# Sheet1.net
KiCad netlist of a schematic drawn in Altium Designer
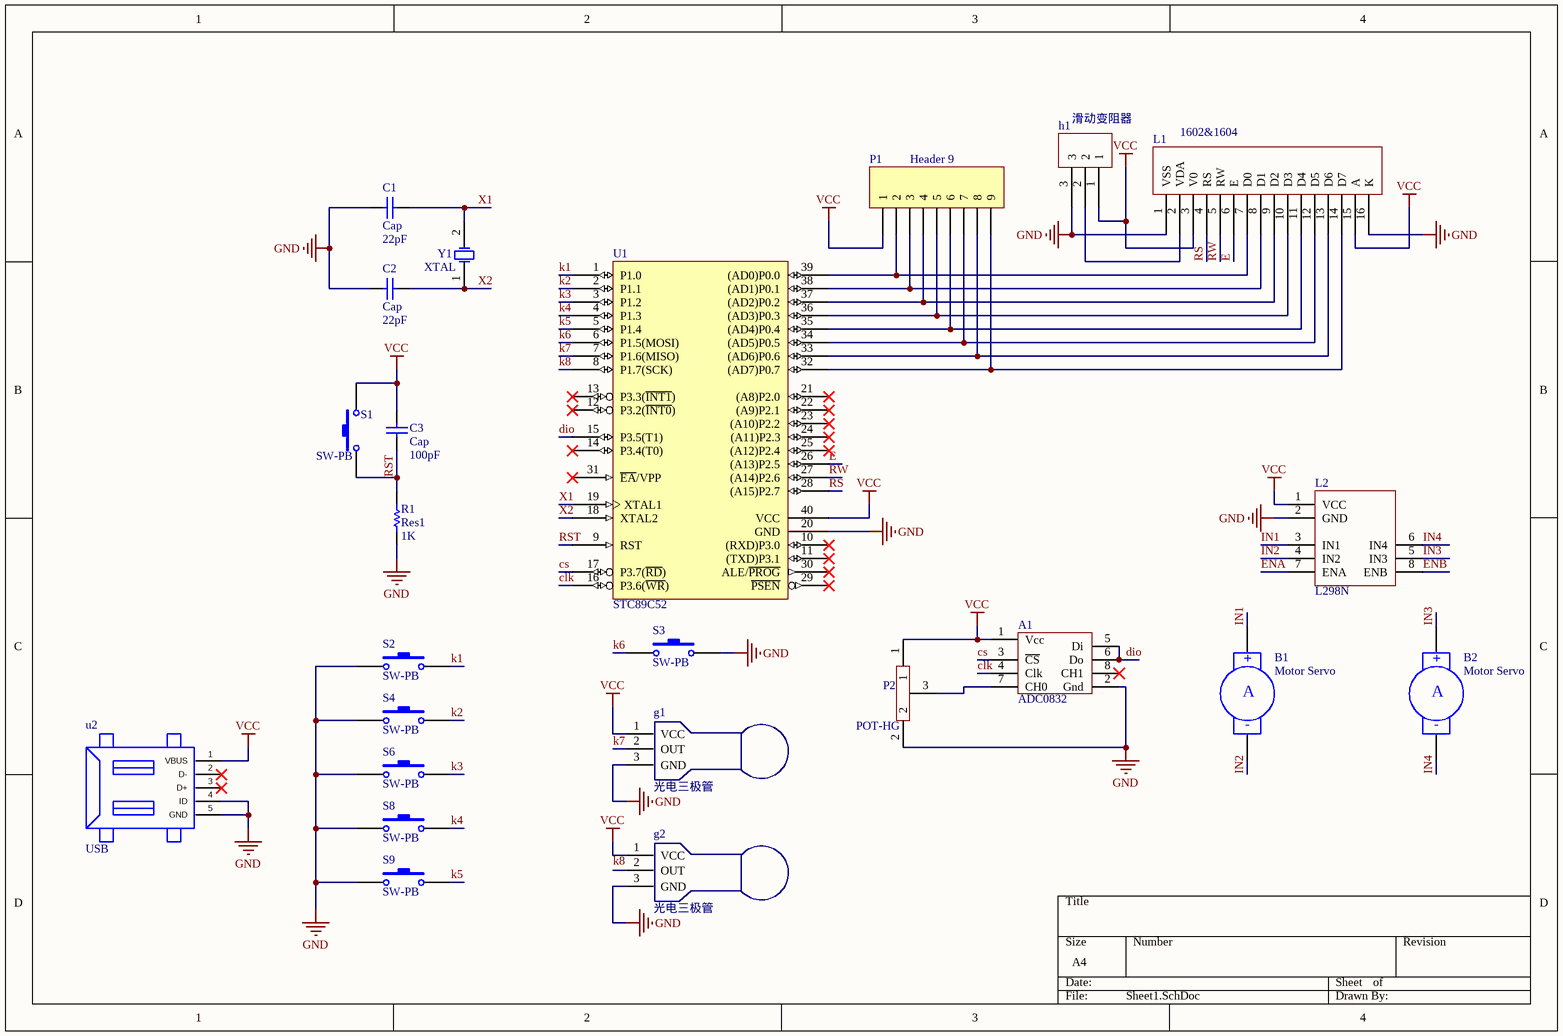
[diagram p0: Sheet1.SchDoc]

(export (version "E")
  (design (tool "Eeschema 10.0.6"))
  (components
    (comp (ref "A1") (value "ADC0832") (libsource (lib "mine") (part "ADC0832")))
    (comp (ref "B1")
      (value "Motor Servo")
      (footprint "RAD-0.4")
      (description "Servo Motor")
      (fields (field (name "PUBLISHER") "Altium Limited"))
      (libsource (lib "Miscellaneous Devices") (part "Motor Servo"))
    )
    (comp (ref "B2")
      (value "Motor Servo")
      (footprint "RAD-0.4")
      (description "Servo Motor")
      (fields (field (name "PUBLISHER") "Altium Limited"))
      (libsource (lib "Miscellaneous Devices") (part "Motor Servo"))
    )
    (comp (ref "C1")
      (value "Cap")
      (footprint "RAD-0.3")
      (description "Capacitor")
      (fields (field (name "ALTIUM_VALUE") "22pF") (field (name "PUBLISHER") "Altium Limited"))
      (libsource (lib "Miscellaneous Devices") (part "Cap"))
    )
    (comp (ref "C2")
      (value "Cap")
      (footprint "RAD-0.3")
      (description "Capacitor")
      (fields (field (name "ALTIUM_VALUE") "22pF") (field (name "PUBLISHER") "Altium Limited"))
      (libsource (lib "Miscellaneous Devices") (part "Cap"))
    )
    (comp (ref "C3")
      (value "Cap")
      (footprint "RAD-0.3")
      (description "Capacitor")
      (fields (field (name "ALTIUM_VALUE") "100pF") (field (name "PUBLISHER") "Altium Limited"))
      (libsource (lib "Miscellaneous Devices") (part "Cap"))
    )
    (comp (ref "g1") (value "光电三极管") (libsource (lib "mine") (part "光电三极管")))
    (comp (ref "g2") (value "光电三极管") (libsource (lib "mine") (part "光电三极管")))
    (comp (ref "h1") (value "滑动变阻器") (libsource (lib "mine") (part "滑动变阻器")))
    (comp (ref "L1") (value "1602&1604") (libsource (lib "mine") (part "1602&1604")))
    (comp (ref "L2") (value "L298N") (libsource (lib "mine") (part "L298N")))
    (comp (ref "P1")
      (value "Header 9")
      (footprint "HDR1X9")
      (description "Header, 9-Pin")
      (fields (field (name "PUBLISHER") "Altium Limited"))
      (libsource (lib "Miscellaneous Connectors") (part "Header 9"))
    )
    (comp (ref "P2") (value "POT-HG") (libsource (lib "mine") (part "POT-HG")))
    (comp (ref "R1")
      (value "Res1")
      (footprint "AXIAL-0.3")
      (description "Resistor")
      (fields (field (name "ALTIUM_VALUE") "1K") (field (name "PUBLISHER") "Altium Limited"))
      (libsource (lib "Miscellaneous Devices") (part "Res1"))
    )
    (comp (ref "S1")
      (value "SW-PB")
      (footprint "SPST-2")
      (description "Switch")
      (fields (field (name "PUBLISHER") "Altium Limited"))
      (libsource (lib "Miscellaneous Devices") (part "SW-PB"))
    )
    (comp (ref "S2")
      (value "SW-PB")
      (footprint "SPST-2")
      (description "Switch")
      (fields (field (name "PUBLISHER") "Altium Limited"))
      (libsource (lib "常用器件") (part "SW-PB"))
    )
    (comp (ref "S3")
      (value "SW-PB")
      (footprint "SPST-2")
      (description "Switch")
      (fields (field (name "PUBLISHER") "Altium Limited"))
      (libsource (lib "常用器件") (part "SW-PB"))
    )
    (comp (ref "S4")
      (value "SW-PB")
      (footprint "SPST-2")
      (description "Switch")
      (fields (field (name "PUBLISHER") "Altium Limited"))
      (libsource (lib "常用器件") (part "SW-PB"))
    )
    (comp (ref "S6")
      (value "SW-PB")
      (footprint "SPST-2")
      (description "Switch")
      (fields (field (name "PUBLISHER") "Altium Limited"))
      (libsource (lib "常用器件") (part "SW-PB"))
    )
    (comp (ref "S8")
      (value "SW-PB")
      (footprint "SPST-2")
      (description "Switch")
      (fields (field (name "PUBLISHER") "Altium Limited"))
      (libsource (lib "常用器件") (part "SW-PB"))
    )
    (comp (ref "S9")
      (value "SW-PB")
      (footprint "SPST-2")
      (description "Switch")
      (fields (field (name "PUBLISHER") "Altium Limited"))
      (libsource (lib "常用器件") (part "SW-PB"))
    )
    (comp (ref "U1")
      (value "STC89C52")
      (footprint "DIP-40")
      (description "8-Bit Microcontroller with 4K ISP Flash ROM")
      (libsource (lib "单片机8051") (part "AT89S51"))
    )
    (comp (ref "u2") (value "USB") (libsource (lib "mine") (part "USB")))
    (comp (ref "Y1")
      (value "XTAL")
      (footprint "R38")
      (description "Crystal Oscillator")
      (fields (field (name "PUBLISHER") "Altium Limited"))
      (libsource (lib "Miscellaneous Devices") (part "XTAL"))
    )
  )
  (nets
    (net (code "1") (name "/E") (class "Default")
      (node (ref "L1") (pin "6") (pinfunction "E_6") (pintype "passive"))
      (node (ref "U1") (pin "26") (pinfunction "(A13)P2.5_26") (pintype "bidirectional"))
    )
    (net (code "2") (name "/ENA") (class "Default")
      (node (ref "L2") (pin "7") (pinfunction "ENA_7") (pintype "passive"))
    )
    (net (code "3") (name "/ENB") (class "Default")
      (node (ref "L2") (pin "8") (pinfunction "ENB_8") (pintype "passive"))
    )
    (net (code "4") (name "/IN1") (class "Default")
      (node (ref "B1") (pin "1") (pinfunction "+_1") (pintype "passive"))
      (node (ref "L2") (pin "3") (pinfunction "IN1_3") (pintype "passive"))
    )
    (net (code "5") (name "/IN2") (class "Default")
      (node (ref "B1") (pin "2") (pinfunction "-_2") (pintype "passive"))
      (node (ref "L2") (pin "4") (pinfunction "IN2_4") (pintype "passive"))
    )
    (net (code "6") (name "/IN3") (class "Default")
      (node (ref "B2") (pin "1") (pinfunction "+_1") (pintype "passive"))
      (node (ref "L2") (pin "5") (pinfunction "IN3_5") (pintype "passive"))
    )
    (net (code "7") (name "/IN4") (class "Default")
      (node (ref "B2") (pin "2") (pinfunction "-_2") (pintype "passive"))
      (node (ref "L2") (pin "6") (pinfunction "IN4_6") (pintype "passive"))
    )
    (net (code "8") (name "/RS") (class "Default")
      (node (ref "L1") (pin "4") (pinfunction "RS_4") (pintype "passive"))
      (node (ref "U1") (pin "28") (pinfunction "(A15)P2.7_28") (pintype "bidirectional"))
    )
    (net (code "9") (name "/RST") (class "Default")
      (node (ref "C3") (pin "1") (pinfunction "1_1") (pintype "passive"))
      (node (ref "R1") (pin "2") (pinfunction "2_2") (pintype "passive"))
      (node (ref "S1") (pin "1") (pinfunction "1_1") (pintype "passive"))
      (node (ref "U1") (pin "9") (pinfunction "RST_9") (pintype "input"))
    )
    (net (code "10") (name "/RW") (class "Default")
      (node (ref "L1") (pin "5") (pinfunction "RW_5") (pintype "passive"))
      (node (ref "U1") (pin "27") (pinfunction "(A14)P2.6_27") (pintype "bidirectional"))
    )
    (net (code "11") (name "/X1") (class "Default")
      (node (ref "C1") (pin "2") (pinfunction "2_2") (pintype "passive"))
      (node (ref "U1") (pin "19") (pinfunction "XTAL1_19") (pintype "input"))
      (node (ref "Y1") (pin "2") (pinfunction "OSC2_2") (pintype "passive"))
    )
    (net (code "12") (name "/X2") (class "Default")
      (node (ref "C2") (pin "2") (pinfunction "2_2") (pintype "passive"))
      (node (ref "U1") (pin "18") (pinfunction "XTAL2_18") (pintype "input"))
      (node (ref "Y1") (pin "1") (pinfunction "OSC1_1") (pintype "passive"))
    )
    (net (code "13") (name "/clk") (class "Default")
      (node (ref "A1") (pin "4") (pinfunction "Clk_4") (pintype "passive"))
      (node (ref "U1") (pin "16") (pinfunction "P3.6(~{WR})_16") (pintype "bidirectional"))
    )
    (net (code "14") (name "/cs") (class "Default")
      (node (ref "A1") (pin "3") (pinfunction "~{CS}_3") (pintype "passive"))
      (node (ref "U1") (pin "17") (pinfunction "P3.7(~{RD})_17") (pintype "bidirectional"))
    )
    (net (code "15") (name "/dio") (class "Default")
      (node (ref "A1") (pin "5") (pinfunction "Di_5") (pintype "passive"))
      (node (ref "A1") (pin "6") (pinfunction "Do_6") (pintype "passive"))
      (node (ref "U1") (pin "15") (pinfunction "P3.5(T1)_15") (pintype "bidirectional"))
    )
    (net (code "16") (name "/k1") (class "Default")
      (node (ref "S2") (pin "2") (pinfunction "2_2") (pintype "passive"))
      (node (ref "U1") (pin "1") (pinfunction "P1.0_1") (pintype "bidirectional"))
    )
    (net (code "17") (name "/k2") (class "Default")
      (node (ref "S4") (pin "2") (pinfunction "2_2") (pintype "passive"))
      (node (ref "U1") (pin "2") (pinfunction "P1.1_2") (pintype "bidirectional"))
    )
    (net (code "18") (name "/k3") (class "Default")
      (node (ref "S6") (pin "2") (pinfunction "2_2") (pintype "passive"))
      (node (ref "U1") (pin "3") (pinfunction "P1.2_3") (pintype "bidirectional"))
    )
    (net (code "19") (name "/k4") (class "Default")
      (node (ref "S8") (pin "2") (pinfunction "2_2") (pintype "passive"))
      (node (ref "U1") (pin "4") (pinfunction "P1.3_4") (pintype "bidirectional"))
    )
    (net (code "20") (name "/k5") (class "Default")
      (node (ref "S9") (pin "2") (pinfunction "2_2") (pintype "passive"))
      (node (ref "U1") (pin "5") (pinfunction "P1.4_5") (pintype "bidirectional"))
    )
    (net (code "21") (name "/k6") (class "Default")
      (node (ref "S3") (pin "1") (pinfunction "1_1") (pintype "passive"))
      (node (ref "U1") (pin "6") (pinfunction "P1.5(MOSI)_6") (pintype "bidirectional"))
    )
    (net (code "22") (name "/k7") (class "Default")
      (node (ref "U1") (pin "7") (pinfunction "P1.6(MISO)_7") (pintype "bidirectional"))
      (node (ref "g1") (pin "2") (pinfunction "OUT_2") (pintype "passive"))
    )
    (net (code "23") (name "/k8") (class "Default")
      (node (ref "U1") (pin "8") (pinfunction "P1.7(SCK)_8") (pintype "bidirectional"))
    )
    (net (code "24") (name "GND") (class "Default")
      (node (ref "A1") (pin "2") (pinfunction "Gnd_2") (pintype "passive"))
      (node (ref "C1") (pin "1") (pinfunction "1_1") (pintype "passive"))
      (node (ref "C2") (pin "1") (pinfunction "1_1") (pintype "passive"))
      (node (ref "L1") (pin "1") (pinfunction "VSS_1") (pintype "passive"))
      (node (ref "L1") (pin "16") (pinfunction "K_16") (pintype "passive"))
      (node (ref "L2") (pin "2") (pinfunction "GND_2") (pintype "passive"))
      (node (ref "P2") (pin "2") (pinfunction "2_2") (pintype "passive"))
      (node (ref "R1") (pin "1") (pinfunction "1_1") (pintype "passive"))
      (node (ref "S2") (pin "1") (pinfunction "1_1") (pintype "passive"))
      (node (ref "S3") (pin "2") (pinfunction "2_2") (pintype "passive"))
      (node (ref "S4") (pin "1") (pinfunction "1_1") (pintype "passive"))
      (node (ref "S6") (pin "1") (pinfunction "1_1") (pintype "passive"))
      (node (ref "S8") (pin "1") (pinfunction "1_1") (pintype "passive"))
      (node (ref "S9") (pin "1") (pinfunction "1_1") (pintype "passive"))
      (node (ref "U1") (pin "20") (pinfunction "GND_20") (pintype "power_in"))
      (node (ref "g1") (pin "3") (pinfunction "GND_3") (pintype "passive"))
      (node (ref "g2") (pin "3") (pinfunction "GND_3") (pintype "passive"))
      (node (ref "h1") (pin "3") (pinfunction "3_3") (pintype "passive"))
      (node (ref "u2") (pin "4") (pinfunction "ID_4") (pintype "passive"))
      (node (ref "u2") (pin "5") (pinfunction "GND_5") (pintype "passive"))
    )
    (net (code "25") (name "Net-(A1-CH0)") (class "Default")
      (node (ref "A1") (pin "7") (pinfunction "CH0_7") (pintype "passive"))
      (node (ref "P2") (pin "3") (pintype "passive"))
    )
    (net (code "26") (name "Net-(L1-D0)") (class "Default")
      (node (ref "L1") (pin "7") (pinfunction "D0_7") (pintype "passive"))
      (node (ref "P1") (pin "2") (pinfunction "2_2") (pintype "passive"))
      (node (ref "U1") (pin "39") (pinfunction "(AD0)P0.0_39") (pintype "bidirectional"))
    )
    (net (code "27") (name "Net-(L1-D1)") (class "Default")
      (node (ref "L1") (pin "8") (pinfunction "D1_8") (pintype "passive"))
      (node (ref "P1") (pin "3") (pinfunction "3_3") (pintype "passive"))
      (node (ref "U1") (pin "38") (pinfunction "(AD1)P0.1_38") (pintype "bidirectional"))
    )
    (net (code "28") (name "Net-(L1-D2)") (class "Default")
      (node (ref "L1") (pin "9") (pinfunction "D2_9") (pintype "passive"))
      (node (ref "P1") (pin "4") (pinfunction "4_4") (pintype "passive"))
      (node (ref "U1") (pin "37") (pinfunction "(AD2)P0.2_37") (pintype "bidirectional"))
    )
    (net (code "29") (name "Net-(L1-D3)") (class "Default")
      (node (ref "L1") (pin "10") (pinfunction "D3_10") (pintype "passive"))
      (node (ref "P1") (pin "5") (pinfunction "5_5") (pintype "passive"))
      (node (ref "U1") (pin "36") (pinfunction "(AD3)P0.3_36") (pintype "bidirectional"))
    )
    (net (code "30") (name "Net-(L1-D4)") (class "Default")
      (node (ref "L1") (pin "11") (pinfunction "D4_11") (pintype "passive"))
      (node (ref "P1") (pin "6") (pinfunction "6_6") (pintype "passive"))
      (node (ref "U1") (pin "35") (pinfunction "(AD4)P0.4_35") (pintype "bidirectional"))
    )
    (net (code "31") (name "Net-(L1-D5)") (class "Default")
      (node (ref "L1") (pin "12") (pinfunction "D5_12") (pintype "passive"))
      (node (ref "P1") (pin "7") (pinfunction "7_7") (pintype "passive"))
      (node (ref "U1") (pin "34") (pinfunction "(AD5)P0.5_34") (pintype "bidirectional"))
    )
    (net (code "32") (name "Net-(L1-D6)") (class "Default")
      (node (ref "L1") (pin "13") (pinfunction "D6_13") (pintype "passive"))
      (node (ref "P1") (pin "8") (pinfunction "8_8") (pintype "passive"))
      (node (ref "U1") (pin "33") (pinfunction "(AD6)P0.6_33") (pintype "bidirectional"))
    )
    (net (code "33") (name "Net-(L1-D7)") (class "Default")
      (node (ref "L1") (pin "14") (pinfunction "D7_14") (pintype "passive"))
      (node (ref "P1") (pin "9") (pinfunction "9_9") (pintype "passive"))
      (node (ref "U1") (pin "32") (pinfunction "(AD7)P0.7_32") (pintype "bidirectional"))
    )
    (net (code "34") (name "Net-(L1-VDA)") (class "Default")
      (node (ref "L1") (pin "2") (pinfunction "VDA_2") (pintype "passive"))
      (node (ref "h1") (pin "2") (pinfunction "2_2") (pintype "passive"))
    )
    (net (code "35") (name "VCC") (class "Default")
      (node (ref "A1") (pin "1") (pinfunction "Vcc_1") (pintype "passive"))
      (node (ref "C3") (pin "2") (pinfunction "2_2") (pintype "passive"))
      (node (ref "L1") (pin "15") (pinfunction "A_15") (pintype "passive"))
      (node (ref "L1") (pin "3") (pinfunction "V0_3") (pintype "passive"))
      (node (ref "L2") (pin "1") (pinfunction "VCC_1") (pintype "passive"))
      (node (ref "P1") (pin "1") (pinfunction "1_1") (pintype "passive"))
      (node (ref "P2") (pin "1") (pinfunction "1_1") (pintype "passive"))
      (node (ref "S1") (pin "2") (pinfunction "2_2") (pintype "passive"))
      (node (ref "U1") (pin "40") (pinfunction "VCC_40") (pintype "power_in"))
      (node (ref "g1") (pin "1") (pinfunction "VCC_1") (pintype "passive"))
      (node (ref "g2") (pin "1") (pinfunction "VCC_1") (pintype "passive"))
      (node (ref "h1") (pin "1") (pinfunction "1_1") (pintype "passive"))
      (node (ref "u2") (pin "1") (pinfunction "VBUS_1") (pintype "passive"))
    )
    (net (code "36") (name "unconnected-(A1-CH1-Pad8)") (class "Default")
      (node (ref "A1") (pin "8") (pinfunction "CH1_8") (pintype "passive+no_connect"))
    )
    (net (code "37") (name "unconnected-(U1-(A8)P2.0-Pad21)") (class "Default")
      (node (ref "U1") (pin "21") (pinfunction "(A8)P2.0_21") (pintype "bidirectional+no_connect"))
    )
    (net (code "38") (name "unconnected-(U1-(A9)P2.1-Pad22)") (class "Default")
      (node (ref "U1") (pin "22") (pinfunction "(A9)P2.1_22") (pintype "bidirectional+no_connect"))
    )
    (net (code "39") (name "unconnected-(U1-(A10)P2.2-Pad23)") (class "Default")
      (node (ref "U1") (pin "23") (pinfunction "(A10)P2.2_23") (pintype "bidirectional+no_connect"))
    )
    (net (code "40") (name "unconnected-(U1-(A11)P2.3-Pad24)") (class "Default")
      (node (ref "U1") (pin "24") (pinfunction "(A11)P2.3_24") (pintype "bidirectional+no_connect"))
    )
    (net (code "41") (name "unconnected-(U1-(A12)P2.4-Pad25)") (class "Default")
      (node (ref "U1") (pin "25") (pinfunction "(A12)P2.4_25") (pintype "bidirectional+no_connect"))
    )
    (net (code "42") (name "unconnected-(U1-(RXD)P3.0-Pad10)") (class "Default")
      (node (ref "U1") (pin "10") (pinfunction "(RXD)P3.0_10") (pintype "bidirectional+no_connect"))
    )
    (net (code "43") (name "unconnected-(U1-(TXD)P3.1-Pad11)") (class "Default")
      (node (ref "U1") (pin "11") (pinfunction "(TXD)P3.1_11") (pintype "bidirectional+no_connect"))
    )
    (net (code "44") (name "unconnected-(U1-ALE{slash}~{PROG}-Pad30)") (class "Default")
      (node (ref "U1") (pin "30") (pinfunction "ALE/~{PROG}_30") (pintype "output+no_connect"))
    )
    (net (code "45") (name "unconnected-(U1-P3.2(~{INT0})-Pad12)") (class "Default")
      (node (ref "U1") (pin "12") (pinfunction "P3.2(~{INT0})_12") (pintype "bidirectional+no_connect"))
    )
    (net (code "46") (name "unconnected-(U1-P3.3(~{INT1})-Pad13)") (class "Default")
      (node (ref "U1") (pin "13") (pinfunction "P3.3(~{INT1})_13") (pintype "bidirectional+no_connect"))
    )
    (net (code "47") (name "unconnected-(U1-P3.4(T0)-Pad14)") (class "Default")
      (node (ref "U1") (pin "14") (pinfunction "P3.4(T0)_14") (pintype "bidirectional+no_connect"))
    )
    (net (code "48") (name "unconnected-(U1-~{EA}{slash}VPP-Pad31)") (class "Default")
      (node (ref "U1") (pin "31") (pinfunction "~{EA}/VPP_31") (pintype "input+no_connect"))
    )
    (net (code "49") (name "unconnected-(U1-~{PSEN}-Pad29)") (class "Default")
      (node (ref "U1") (pin "29") (pinfunction "~{PSEN}_29") (pintype "output+no_connect"))
    )
    (net (code "50") (name "unconnected-(g2-OUT-Pad2)") (class "Default")
      (node (ref "g2") (pin "2") (pinfunction "OUT_2") (pintype "passive"))
    )
    (net (code "51") (name "unconnected-(u2-D+-Pad3)") (class "Default")
      (node (ref "u2") (pin "3") (pinfunction "D+_3") (pintype "passive+no_connect"))
    )
    (net (code "52") (name "unconnected-(u2-D--Pad2)") (class "Default")
      (node (ref "u2") (pin "2") (pinfunction "D-_2") (pintype "passive+no_connect"))
    )
  )
)
